# Conn.net
KiCad netlist of a schematic drawn in Altium Designer
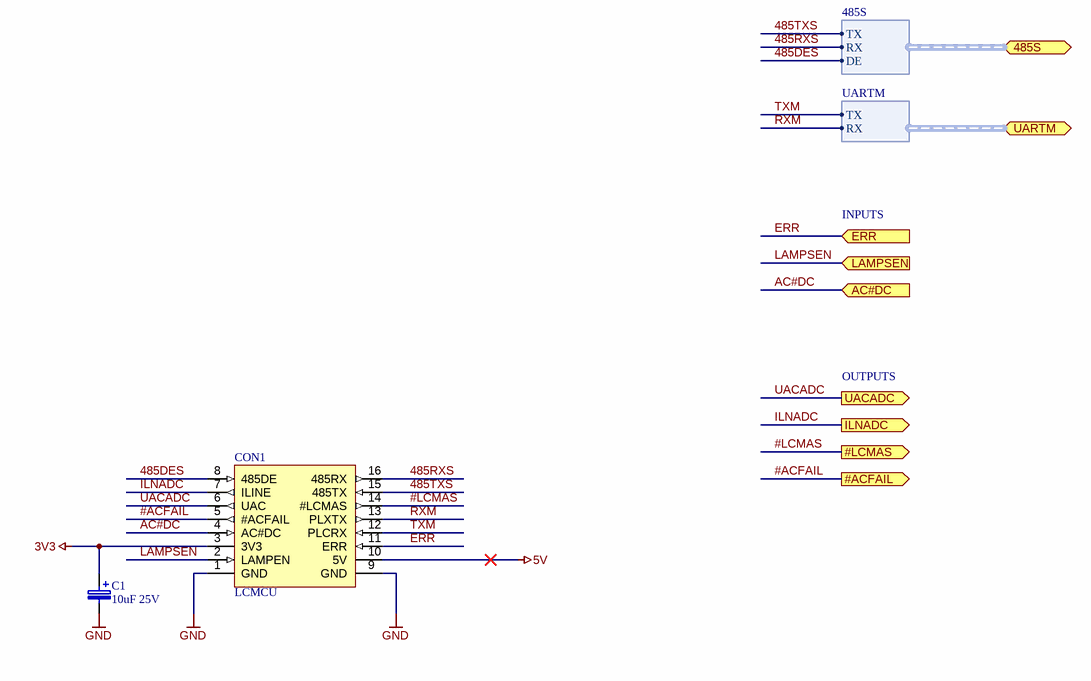
[diagram p0: Conn.SchDoc]

(export (version "E")
  (design (tool "Eeschema 10.0.6"))
  (components
    (comp (ref "C1")
      (value "10uF 25V")
      (footprint "SMDB")
      (description "Capacitor Tantalum")
      (libsource (lib "Discrete") (part "Capacitor Tantalum"))
    )
    (comp (ref "CON1")
      (value "LCMCU")
      (footprint "IDC_FEM_BOT_16")
      (libsource (lib "specific") (part "LCMCU"))
    )
  )
  (nets
    (net (code "3") (name "/#ACFAIL") (class "Default")
      (node (ref "CON1") (pin "5") (pinfunction "#ACFAIL_5") (pintype "output"))
    )
    (net (code "4") (name "/#LCMAS") (class "Default")
      (node (ref "CON1") (pin "14") (pinfunction "#LCMAS_14") (pintype "output"))
    )
    (net (code "5") (name "/485DES") (class "Default")
      (node (ref "CON1") (pin "8") (pinfunction "485DE_8") (pintype "input"))
    )
    (net (code "6") (name "/485RXS") (class "Default")
      (node (ref "CON1") (pin "16") (pinfunction "485RX_16") (pintype "output"))
    )
    (net (code "7") (name "/485TXS") (class "Default")
      (node (ref "CON1") (pin "15") (pinfunction "485TX_15") (pintype "input"))
    )
    (net (code "8") (name "/AC#DC") (class "Default")
      (node (ref "CON1") (pin "4") (pinfunction "AC#DC_4") (pintype "input"))
    )
    (net (code "9") (name "/ERR") (class "Default")
      (node (ref "CON1") (pin "11") (pinfunction "ERR_11") (pintype "input"))
    )
    (net (code "10") (name "/ILNADC") (class "Default")
      (node (ref "CON1") (pin "7") (pinfunction "ILINE_7") (pintype "output"))
    )
    (net (code "11") (name "/LAMPSEN") (class "Default")
      (node (ref "CON1") (pin "2") (pinfunction "LAMPEN_2") (pintype "input"))
    )
    (net (code "12") (name "/RXM") (class "Default")
      (node (ref "CON1") (pin "13") (pinfunction "PLXTX_13") (pintype "output"))
    )
    (net (code "13") (name "/TXM") (class "Default")
      (node (ref "CON1") (pin "12") (pinfunction "PLCRX_12") (pintype "input"))
    )
    (net (code "14") (name "/UACADC") (class "Default")
      (node (ref "CON1") (pin "6") (pinfunction "UAC_6") (pintype "output"))
    )
    (net (code "17") (name "3V3") (class "Default")
      (node (ref "C1") (pin "1") (pinfunction "1_1") (pintype "passive"))
      (node (ref "CON1") (pin "3") (pinfunction "3V3_3") (pintype "power_in"))
    )
    (net (code "18") (name "5V") (class "Default")
      (node (ref "CON1") (pin "10") (pinfunction "5V_10") (pintype "power_in"))
    )
    (net (code "19") (name "GND") (class "Default")
      (node (ref "C1") (pin "2") (pinfunction "2_2") (pintype "passive"))
      (node (ref "CON1") (pin "1") (pinfunction "GND_1") (pintype "power_in"))
      (node (ref "CON1") (pin "9") (pinfunction "GND_9") (pintype "power_in"))
    )
  )
)
